# TCRT1010_VIS_onechannel.net
KiCad netlist of a schematic drawn in EAGLE
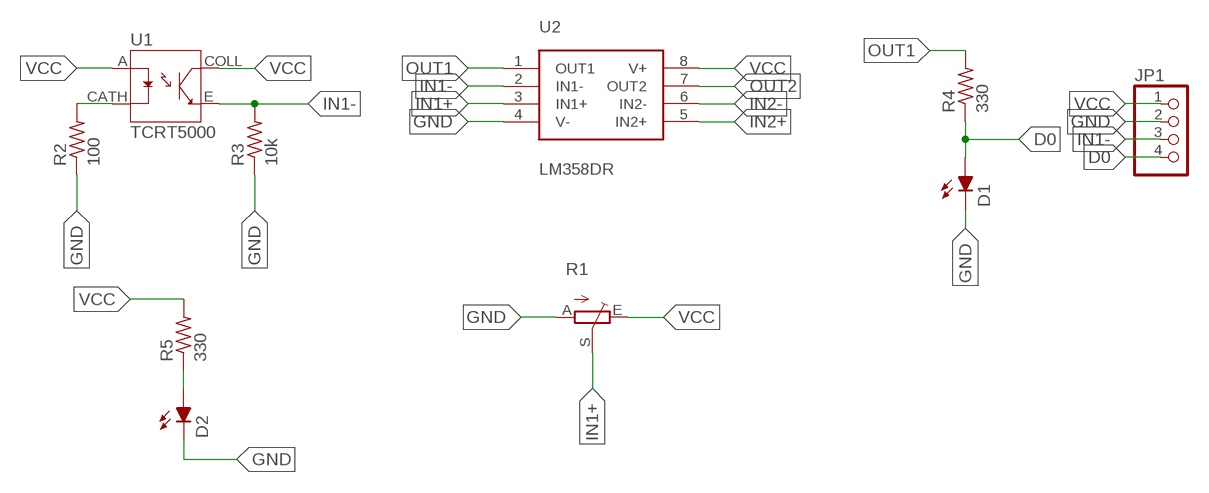
[diagram p0: schematic, sheet 1]

(export (version "E")
  (design (tool "Eeschema 10.0.6"))
  (components
    (comp (ref "D1")
      (value "LED_LEDCHIP-LED0603MP")
      (footprint "eagle-import:LED_CHIP-LED0603MP")
      (libsource (lib "eagle-import") (part "LED_LEDCHIP-LED0603MP"))
    )
    (comp (ref "D2")
      (value "LED_LEDCHIP-LED0603MP")
      (footprint "eagle-import:LED_CHIP-LED0603MP")
      (libsource (lib "eagle-import") (part "LED_LEDCHIP-LED0603MP"))
    )
    (comp (ref "JP1")
      (value "PINHD-1X4")
      (footprint "eagle-import:1X04")
      (libsource (lib "eagle-import") (part "PINHD-1X4"))
    )
    (comp (ref "R1")
      (value "TRIM_EU-CA6V")
      (footprint "eagle-import:CA6V")
      (libsource (lib "eagle-import") (part "TRIM_EU-CA6V"))
    )
    (comp (ref "R2")
      (value "100")
      (footprint "eagle-import:R0805")
      (libsource (lib "eagle-import") (part "R-US_R0805"))
    )
    (comp (ref "R3")
      (value "10k")
      (footprint "eagle-import:R0603")
      (libsource (lib "eagle-import") (part "R-US_R0603"))
    )
    (comp (ref "R4")
      (value "330")
      (footprint "eagle-import:R0603")
      (libsource (lib "eagle-import") (part "R-US_R0603"))
    )
    (comp (ref "R5")
      (value "330")
      (footprint "eagle-import:R0603")
      (libsource (lib "eagle-import") (part "R-US_R0603"))
    )
    (comp (ref "U1")
      (value "TCRT5000")
      (footprint "eagle-import:OPTO_TCRT5000")
      (fields (field (name "MF") "Vishay"))
      (libsource (lib "eagle-import") (part "TCRT5000"))
    )
    (comp (ref "U2")
      (value "LM358DR")
      (footprint "eagle-import:LM358DR")
      (fields
        (field (name "DIGIKEY_PART_NUMBER") "296-1014-1-ND")
        (field (name "MANUFACTURER") "Texas Instruments")
        (field (name "CREATED_BY") "PCBLayout.com")
      )
      (libsource (lib "eagle-import") (part "LM358DR"))
    )
  )
  (nets
    (net (code "1") (name "D0") (class "Default")
      (node (ref "D1") (pin "A") (pinfunction "A_A") (pintype "passive"))
      (node (ref "JP1") (pin "4") (pinfunction "4_4") (pintype "passive"))
      (node (ref "R4") (pin "1") (pinfunction "1_1") (pintype "passive"))
    )
    (net (code "2") (name "GND") (class "Default")
      (node (ref "D1") (pin "C") (pinfunction "C_C") (pintype "passive"))
      (node (ref "D2") (pin "C") (pinfunction "C_C") (pintype "passive"))
      (node (ref "JP1") (pin "2") (pinfunction "2_2") (pintype "passive"))
      (node (ref "R1") (pin "A") (pinfunction "A_A") (pintype "passive"))
      (node (ref "R2") (pin "1") (pinfunction "1_1") (pintype "passive"))
      (node (ref "R3") (pin "1") (pinfunction "1_1") (pintype "passive"))
      (node (ref "U2") (pin "4") (pinfunction "V-_4") (pintype "power_in"))
    )
    (net (code "3") (name "IN1+") (class "Default")
      (node (ref "R1") (pin "S") (pinfunction "S_S") (pintype "passive"))
      (node (ref "U2") (pin "3") (pinfunction "IN1+_3") (pintype "input"))
    )
    (net (code "4") (name "IN1-") (class "Default")
      (node (ref "JP1") (pin "3") (pinfunction "3_3") (pintype "passive"))
      (node (ref "R3") (pin "2") (pinfunction "2_2") (pintype "passive"))
      (node (ref "U1") (pin "E") (pinfunction "E_E") (pintype "passive"))
      (node (ref "U2") (pin "2") (pinfunction "IN1-_2") (pintype "input"))
    )
    (net (code "5") (name "IN2+") (class "Default")
      (node (ref "U2") (pin "5") (pinfunction "IN2+_5") (pintype "input"))
    )
    (net (code "6") (name "IN2-") (class "Default")
      (node (ref "U2") (pin "6") (pinfunction "IN2-_6") (pintype "input"))
    )
    (net (code "7") (name "Net-(D2-PadA)") (class "Default")
      (node (ref "D2") (pin "A") (pinfunction "A_A") (pintype "passive"))
      (node (ref "R5") (pin "1") (pinfunction "1_1") (pintype "passive"))
    )
    (net (code "8") (name "Net-(R2-Pad2)") (class "Default")
      (node (ref "R2") (pin "2") (pinfunction "2_2") (pintype "passive"))
      (node (ref "U1") (pin "CATH") (pinfunction "CATH_CATH") (pintype "passive"))
    )
    (net (code "9") (name "OUT1") (class "Default")
      (node (ref "R4") (pin "2") (pinfunction "2_2") (pintype "passive"))
      (node (ref "U2") (pin "1") (pinfunction "OUT1_1") (pintype "output"))
    )
    (net (code "10") (name "OUT2") (class "Default")
      (node (ref "U2") (pin "7") (pinfunction "OUT2_7") (pintype "output"))
    )
    (net (code "11") (name "VCC") (class "Default")
      (node (ref "JP1") (pin "1") (pinfunction "1_1") (pintype "passive"))
      (node (ref "R1") (pin "E") (pinfunction "E_E") (pintype "passive"))
      (node (ref "R5") (pin "2") (pinfunction "2_2") (pintype "passive"))
      (node (ref "U1") (pin "A") (pinfunction "A_A") (pintype "passive"))
      (node (ref "U1") (pin "COLL") (pinfunction "COLL_COLL") (pintype "passive"))
      (node (ref "U2") (pin "8") (pinfunction "V+_8") (pintype "power_in"))
    )
  )
)
